# SDC_1.net
KiCad netlist of a schematic drawn in Altium Designer
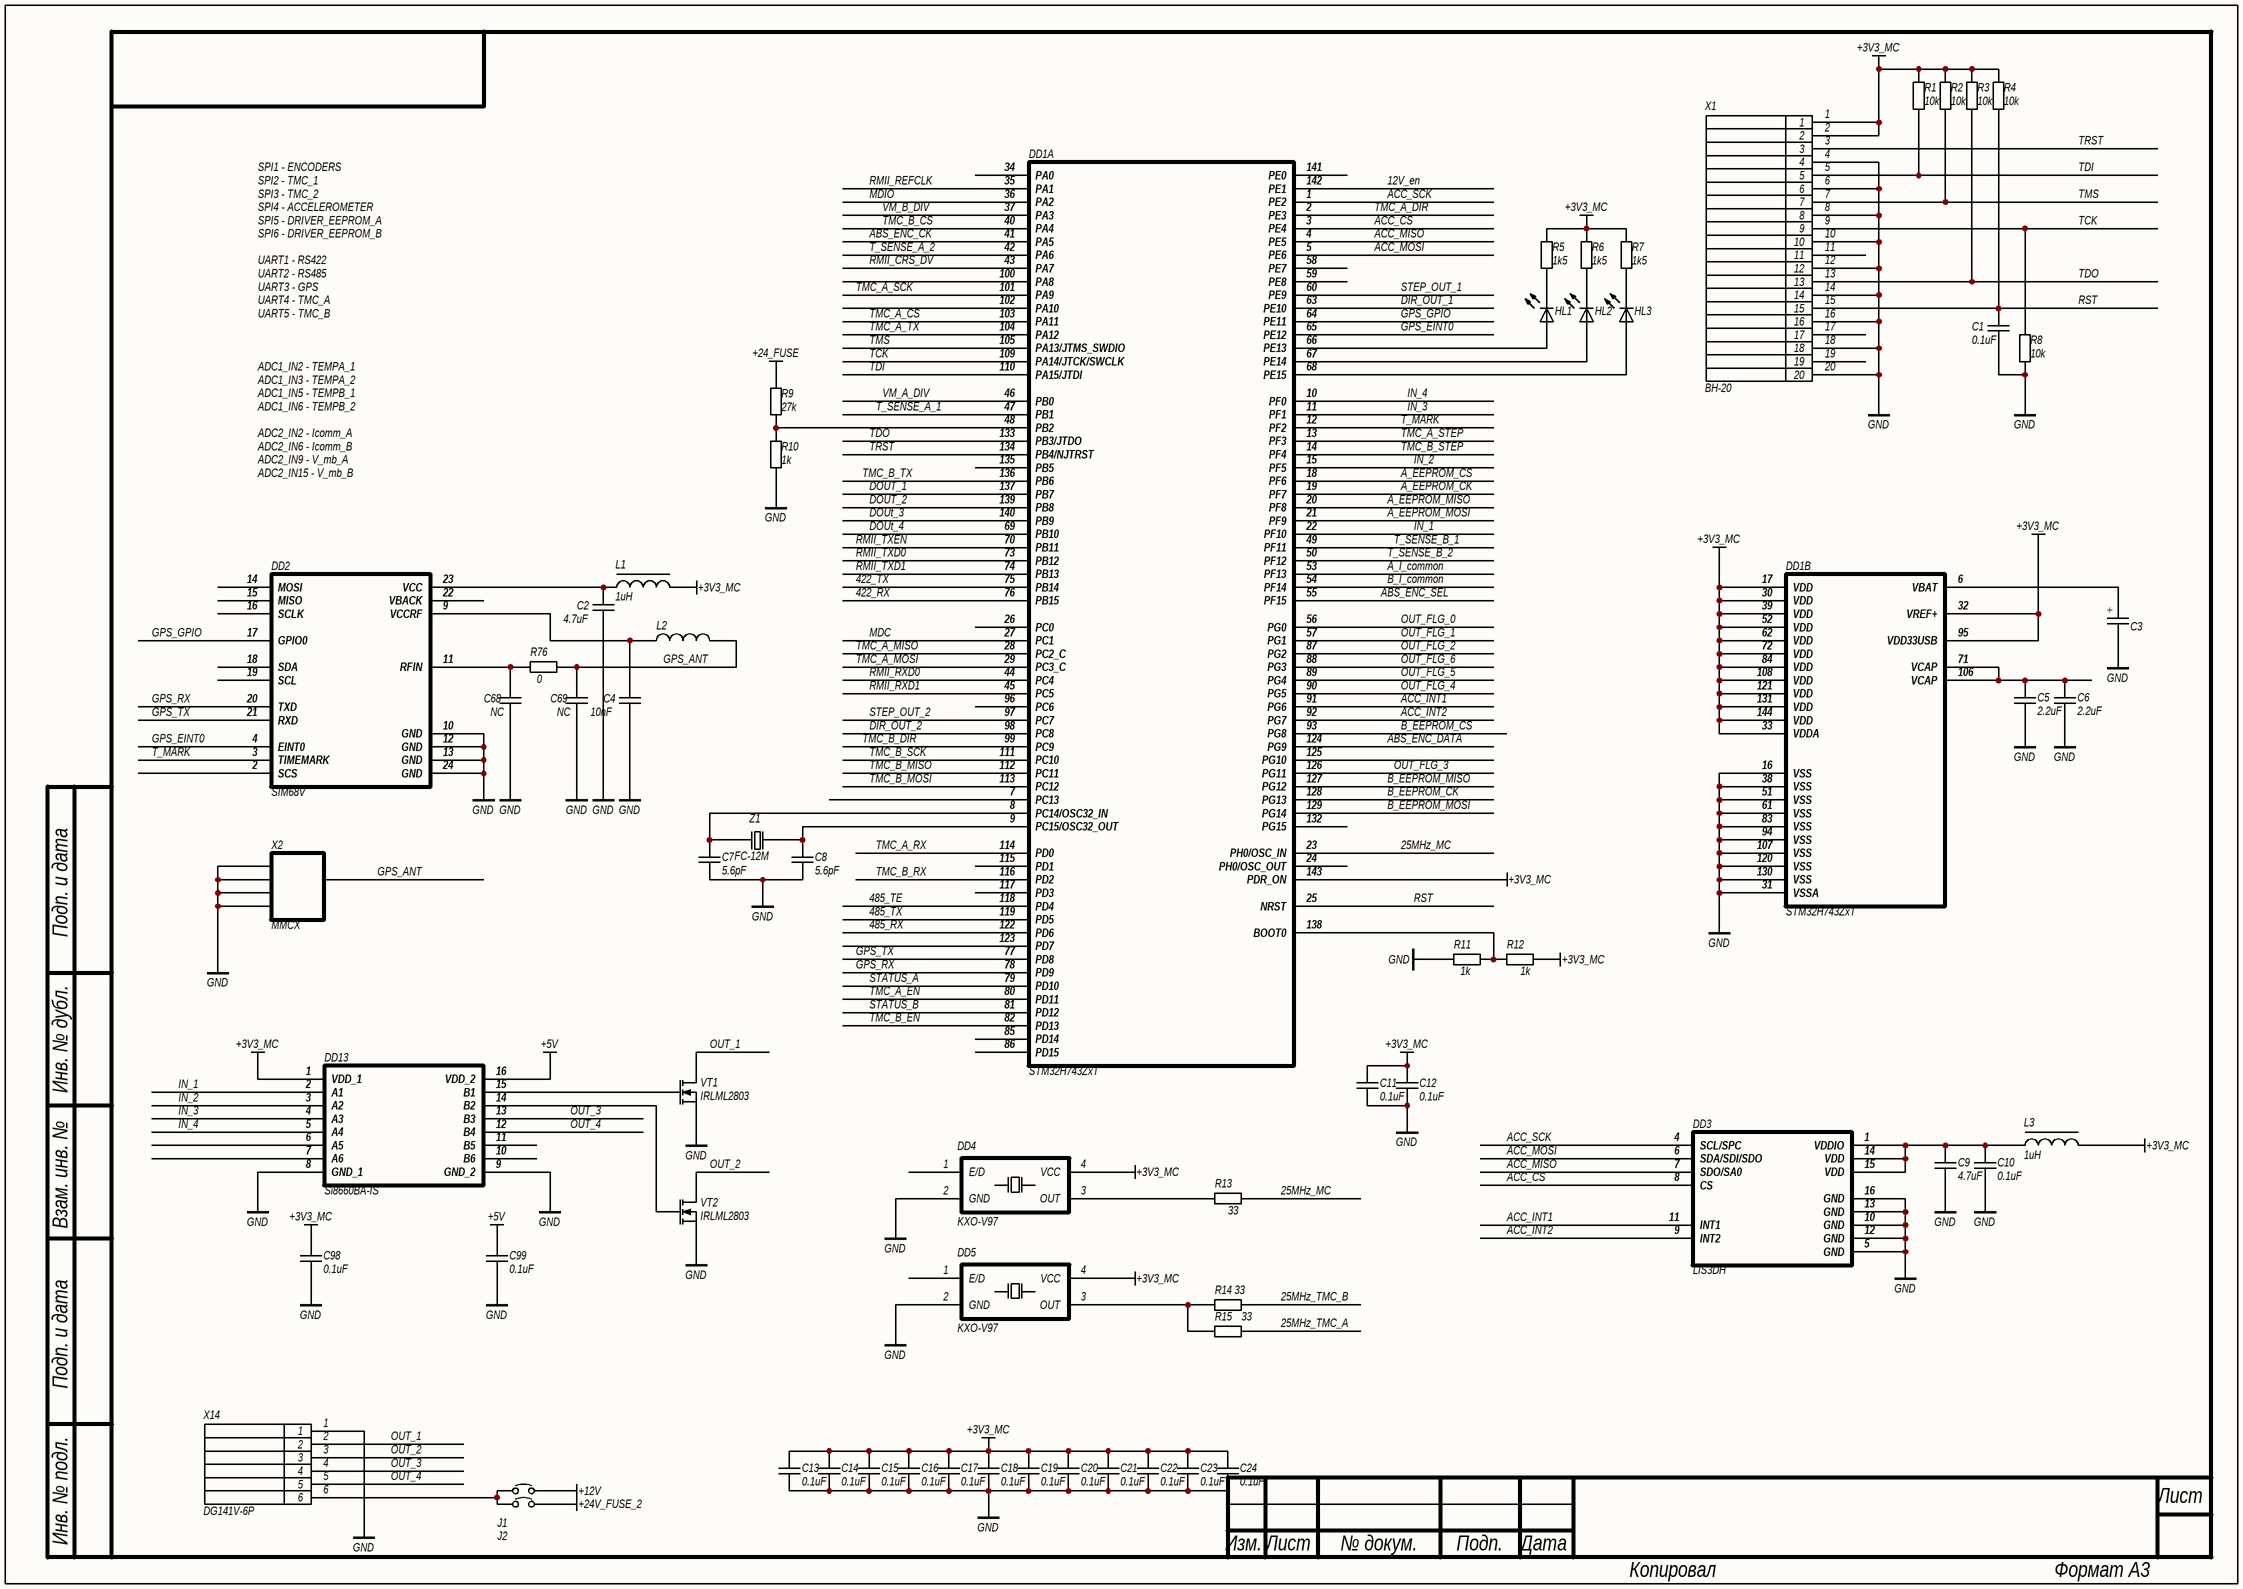
[diagram p0: SDC_1.SchDoc]

(export (version "E")
  (design (tool "Eeschema 10.0.6"))
  (components
    (comp (ref "C1")
      (value "0.1uF")
      (footprint "C0603")
      (description "SMD Capacitor")
      (fields (field (name "MANUFACTURER") "Murata") (field (name "TOLERANCE") "10%"))
      (libsource (lib "VKA") (part "CAP"))
    )
    (comp (ref "C2")
      (value "4.7uF")
      (footprint "C0603")
      (description "SMD Capacitor")
      (fields (field (name "MANUFACTURER") "Murata") (field (name "TOLERANCE") "10%"))
      (libsource (lib "VKA") (part "CAP"))
    )
    (comp (ref "C3")
      (value "KR-5R5H155-R")
      (footprint "KR-5R5H155-R")
      (description "Ionistor")
      (fields (field (name "MANUFACTURER") "Murata") (field (name "VOLTAGE") "5V"))
      (libsource (lib "VKA") (part "KR-5R5H155-R"))
    )
    (comp (ref "C4")
      (value "10nF")
      (footprint "C0603")
      (description "SMD Capacitor")
      (fields (field (name "MANUFACTURER") "Murata") (field (name "TOLERANCE") "10%"))
      (libsource (lib "VKA") (part "CAP"))
    )
    (comp (ref "C5")
      (value "2.2uF")
      (footprint "C0603")
      (description "SMD Capacitor")
      (fields (field (name "MANUFACTURER") "Murata") (field (name "TOLERANCE") "10%"))
      (libsource (lib "VKA") (part "CAP"))
    )
    (comp (ref "C6")
      (value "2.2uF")
      (footprint "C0603")
      (description "SMD Capacitor")
      (fields (field (name "MANUFACTURER") "Murata") (field (name "TOLERANCE") "10%"))
      (libsource (lib "VKA") (part "CAP"))
    )
    (comp (ref "C7")
      (value "5.6pF")
      (footprint "C0603")
      (description "SMD Capacitor")
      (fields (field (name "MANUFACTURER") "Murata") (field (name "TOLERANCE") "10%"))
      (libsource (lib "VKA") (part "CAP"))
    )
    (comp (ref "C8")
      (value "5.6pF")
      (footprint "C0603")
      (description "SMD Capacitor")
      (fields (field (name "MANUFACTURER") "Murata") (field (name "TOLERANCE") "10%"))
      (libsource (lib "VKA") (part "CAP"))
    )
    (comp (ref "C9")
      (value "4.7uF")
      (footprint "C0603")
      (description "SMD Capacitor")
      (fields (field (name "MANUFACTURER") "Murata") (field (name "TOLERANCE") "10%"))
      (libsource (lib "VKA") (part "CAP"))
    )
    (comp (ref "C10")
      (value "0.1uF")
      (footprint "C0603")
      (description "SMD Capacitor")
      (fields (field (name "MANUFACTURER") "Murata") (field (name "TOLERANCE") "10%"))
      (libsource (lib "VKA") (part "CAP"))
    )
    (comp (ref "C11")
      (value "0.1uF")
      (footprint "C0603")
      (description "SMD Capacitor")
      (fields (field (name "MANUFACTURER") "Murata") (field (name "TOLERANCE") "10%"))
      (libsource (lib "VKA") (part "CAP"))
    )
    (comp (ref "C12")
      (value "0.1uF")
      (footprint "C0603")
      (description "SMD Capacitor")
      (fields (field (name "MANUFACTURER") "Murata") (field (name "TOLERANCE") "10%"))
      (libsource (lib "VKA") (part "CAP"))
    )
    (comp (ref "C13")
      (value "0.1uF")
      (footprint "C0603")
      (description "SMD Capacitor")
      (fields (field (name "MANUFACTURER") "Murata") (field (name "TOLERANCE") "10%"))
      (libsource (lib "VKA") (part "CAP"))
    )
    (comp (ref "C14")
      (value "0.1uF")
      (footprint "C0603")
      (description "SMD Capacitor")
      (fields (field (name "MANUFACTURER") "Murata") (field (name "TOLERANCE") "10%"))
      (libsource (lib "VKA") (part "CAP"))
    )
    (comp (ref "C15")
      (value "0.1uF")
      (footprint "C0603")
      (description "SMD Capacitor")
      (fields (field (name "MANUFACTURER") "Murata") (field (name "TOLERANCE") "10%"))
      (libsource (lib "VKA") (part "CAP"))
    )
    (comp (ref "C16")
      (value "0.1uF")
      (footprint "C0603")
      (description "SMD Capacitor")
      (fields (field (name "MANUFACTURER") "Murata") (field (name "TOLERANCE") "10%"))
      (libsource (lib "VKA") (part "CAP"))
    )
    (comp (ref "C17")
      (value "0.1uF")
      (footprint "C0603")
      (description "SMD Capacitor")
      (fields (field (name "MANUFACTURER") "Murata") (field (name "TOLERANCE") "10%"))
      (libsource (lib "VKA") (part "CAP"))
    )
    (comp (ref "C18")
      (value "0.1uF")
      (footprint "C0603")
      (description "SMD Capacitor")
      (fields (field (name "MANUFACTURER") "Murata") (field (name "TOLERANCE") "10%"))
      (libsource (lib "VKA") (part "CAP"))
    )
    (comp (ref "C19")
      (value "0.1uF")
      (footprint "C0603")
      (description "SMD Capacitor")
      (fields (field (name "MANUFACTURER") "Murata") (field (name "TOLERANCE") "10%"))
      (libsource (lib "VKA") (part "CAP"))
    )
    (comp (ref "C20")
      (value "0.1uF")
      (footprint "C0603")
      (description "SMD Capacitor")
      (fields (field (name "MANUFACTURER") "Murata") (field (name "TOLERANCE") "10%"))
      (libsource (lib "VKA") (part "CAP"))
    )
    (comp (ref "C21")
      (value "0.1uF")
      (footprint "C0603")
      (description "SMD Capacitor")
      (fields (field (name "MANUFACTURER") "Murata") (field (name "TOLERANCE") "10%"))
      (libsource (lib "VKA") (part "CAP"))
    )
    (comp (ref "C22")
      (value "0.1uF")
      (footprint "C0603")
      (description "SMD Capacitor")
      (fields (field (name "MANUFACTURER") "Murata") (field (name "TOLERANCE") "10%"))
      (libsource (lib "VKA") (part "CAP"))
    )
    (comp (ref "C23")
      (value "0.1uF")
      (footprint "C0603")
      (description "SMD Capacitor")
      (fields (field (name "MANUFACTURER") "Murata") (field (name "TOLERANCE") "10%"))
      (libsource (lib "VKA") (part "CAP"))
    )
    (comp (ref "C24")
      (value "0.1uF")
      (footprint "C0603")
      (description "SMD Capacitor")
      (fields (field (name "MANUFACTURER") "Murata") (field (name "TOLERANCE") "10%"))
      (libsource (lib "VKA") (part "CAP"))
    )
    (comp (ref "C68")
      (value "NC")
      (footprint "C0603")
      (description "SMD Capacitor")
      (fields (field (name "MANUFACTURER") "Murata") (field (name "TOLERANCE") "10%"))
      (libsource (lib "VKA") (part "CAP"))
    )
    (comp (ref "C69")
      (value "NC")
      (footprint "C0603")
      (description "SMD Capacitor")
      (fields (field (name "MANUFACTURER") "Murata") (field (name "TOLERANCE") "10%"))
      (libsource (lib "VKA") (part "CAP"))
    )
    (comp (ref "C98")
      (value "0.1uF")
      (footprint "C0603")
      (description "SMD Capacitor")
      (fields (field (name "MANUFACTURER") "Murata") (field (name "TOLERANCE") "10%"))
      (libsource (lib "VKA") (part "CAP"))
    )
    (comp (ref "C99")
      (value "0.1uF")
      (footprint "C0603")
      (description "SMD Capacitor")
      (fields (field (name "MANUFACTURER") "Murata") (field (name "TOLERANCE") "10%"))
      (libsource (lib "VKA") (part "CAP"))
    )
    (comp (ref "DD1")
      (value "STM32H743ZxT")
      (footprint "STM-LQFP144_L")
      (description "ARM Cortex-M7, 480MHz, 32-bit MCU+FPU, 144-pin LQFP")
      (libsource (lib "VKA") (part "STM32H743ZxT"))
    )
    (comp (ref "DD2")
      (value "SIM68V")
      (footprint "SIM68M")
      (description "GPS module")
      (libsource (lib "VKA") (part "SIM68V"))
    )
    (comp (ref "DD3")
      (value "LIS3DH")
      (footprint "LGA-16")
      (description "Accelerometer")
      (libsource (lib "VKA") (part "LIS3DH"))
    )
    (comp (ref "DD4")
      (value "KXO-V97")
      (footprint "SO4-GEN")
      (description "KXO generator")
      (libsource (lib "VKA") (part "KXO-V97"))
    )
    (comp (ref "DD5")
      (value "KXO-V97")
      (footprint "SO4-GEN")
      (description "KXO generator")
      (libsource (lib "VKA") (part "KXO-V97"))
    )
    (comp (ref "DD13")
      (value "Si8660BA-IS")
      (footprint "SO-16_N")
      (description "digital isolator")
      (libsource (lib "VKA") (part "Si8660BA-IS"))
    )
    (comp (ref "HL1") (value "LED0603") (footprint "LED0603") (libsource (lib "VKA") (part "LED0603")))
    (comp (ref "HL2") (value "LED0603") (footprint "LED0603") (libsource (lib "VKA") (part "LED0603")))
    (comp (ref "HL3") (value "LED0603") (footprint "LED0603") (libsource (lib "VKA") (part "LED0603")))
    (comp (ref "J1") (value "JUMP") (footprint "JUMP") (libsource (lib "VKA") (part "JUMP")))
    (comp (ref "J2") (value "JUMP") (footprint "JUMP") (libsource (lib "VKA") (part "JUMP")))
    (comp (ref "L1")
      (value "1uH")
      (footprint "LQH32CN")
      (description "chip inductor")
      (fields (field (name "Comment") "LQH32CN"))
      (libsource (lib "VKA") (part "LQH32CN"))
    )
    (comp (ref "L2")
      (value "FerriteBead")
      (footprint "L0603")
      (description "SMD Chip ferrite bead 0603")
      (libsource (lib "VKA") (part "FerriteBead"))
    )
    (comp (ref "L3")
      (value "1uH")
      (footprint "LQH32CN")
      (description "chip inductor")
      (fields (field (name "Comment") "LQH32CN"))
      (libsource (lib "VKA") (part "LQH32CN"))
    )
    (comp (ref "R1")
      (value "10k")
      (footprint "R0603")
      (description "SMD Resistor")
      (fields (field (name "POWER") "0.062 Wt") (field (name "TOLERANCE") "5%"))
      (libsource (lib "VKA") (part "RES"))
    )
    (comp (ref "R2")
      (value "10k")
      (footprint "R0603")
      (description "SMD Resistor")
      (fields (field (name "POWER") "0.062 Wt") (field (name "TOLERANCE") "5%"))
      (libsource (lib "VKA") (part "RES"))
    )
    (comp (ref "R3")
      (value "10k")
      (footprint "R0603")
      (description "SMD Resistor")
      (fields (field (name "POWER") "0.062 Wt") (field (name "TOLERANCE") "5%"))
      (libsource (lib "VKA") (part "RES"))
    )
    (comp (ref "R4")
      (value "10k")
      (footprint "R0603")
      (description "SMD Resistor")
      (fields (field (name "POWER") "0.062 Wt") (field (name "TOLERANCE") "5%"))
      (libsource (lib "VKA") (part "RES"))
    )
    (comp (ref "R5")
      (value "1k5")
      (footprint "R0603")
      (description "SMD Resistor")
      (fields (field (name "POWER") "0.062 Wt") (field (name "TOLERANCE") "5%"))
      (libsource (lib "VKA") (part "RES"))
    )
    (comp (ref "R6")
      (value "1k5")
      (footprint "R0603")
      (description "SMD Resistor")
      (fields (field (name "POWER") "0.062 Wt") (field (name "TOLERANCE") "5%"))
      (libsource (lib "VKA") (part "RES"))
    )
    (comp (ref "R7")
      (value "1k5")
      (footprint "R0603")
      (description "SMD Resistor")
      (fields (field (name "POWER") "0.062 Wt") (field (name "TOLERANCE") "5%"))
      (libsource (lib "VKA") (part "RES"))
    )
    (comp (ref "R8")
      (value "10k")
      (footprint "R0603")
      (description "SMD Resistor")
      (fields (field (name "POWER") "0.062 Wt") (field (name "TOLERANCE") "5%"))
      (libsource (lib "VKA") (part "RES"))
    )
    (comp (ref "R9")
      (value "27k")
      (footprint "R0603")
      (description "SMD Resistor")
      (fields (field (name "POWER") "0.062 Wt") (field (name "TOLERANCE") "5%"))
      (libsource (lib "") (part "RES_2"))
    )
    (comp (ref "R10")
      (value "1k")
      (footprint "R0603")
      (description "SMD Resistor")
      (fields (field (name "POWER") "0.062 Wt") (field (name "TOLERANCE") "5%"))
      (libsource (lib "") (part "RES_2"))
    )
    (comp (ref "R11")
      (value "1k")
      (footprint "R0603")
      (description "SMD Resistor")
      (fields (field (name "POWER") "0.062 Wt") (field (name "TOLERANCE") "5%"))
      (libsource (lib "") (part "RES_1"))
    )
    (comp (ref "R12")
      (value "1k")
      (footprint "R0603")
      (description "SMD Resistor")
      (fields (field (name "POWER") "0.062 Wt") (field (name "TOLERANCE") "5%"))
      (libsource (lib "") (part "RES_1"))
    )
    (comp (ref "R13")
      (value "33")
      (footprint "R0603")
      (description "SMD Resistor")
      (fields (field (name "POWER") "0.062 Wt") (field (name "TOLERANCE") "5%"))
      (libsource (lib "") (part "RES_1"))
    )
    (comp (ref "R14")
      (value "33")
      (footprint "R0603")
      (description "SMD Resistor")
      (fields (field (name "POWER") "0.062 Wt") (field (name "TOLERANCE") "5%"))
      (libsource (lib "") (part "RES_1"))
    )
    (comp (ref "R15")
      (value "33")
      (footprint "R0603")
      (description "SMD Resistor")
      (fields (field (name "POWER") "0.062 Wt") (field (name "TOLERANCE") "5%"))
      (libsource (lib "") (part "RES_1"))
    )
    (comp (ref "R76")
      (value "0")
      (footprint "R0603")
      (description "SMD Resistor")
      (fields (field (name "POWER") "0.062 Wt") (field (name "TOLERANCE") "5%"))
      (libsource (lib "") (part "RES_1"))
    )
    (comp (ref "VT1")
      (value "IRLML2803")
      (footprint "SOT23")
      (description "n-channel fet")
      (libsource (lib "VKA") (part "IRLML2803"))
    )
    (comp (ref "VT2")
      (value "IRLML2803")
      (footprint "SOT23")
      (description "n-channel fet")
      (libsource (lib "VKA") (part "IRLML2803"))
    )
    (comp (ref "X1")
      (value "BH-20")
      (footprint "IDC-20(BH-20)")
      (libsource (lib "VKA") (part "IDC10x2_GOST"))
    )
    (comp (ref "X2")
      (value "MMCX")
      (footprint "MMCX")
      (description "Coaxial")
      (libsource (lib "VKA") (part "MMCX"))
    )
    (comp (ref "X14")
      (value "DG141V-6P")
      (footprint "DG141V-06P")
      (description "wire connector")
      (libsource (lib "VKA") (part "DG141V-6P"))
    )
    (comp (ref "Z1")
      (value "FC-12M")
      (footprint "FC-12M")
      (description "Crystal_32_768")
      (libsource (lib "VKA") (part "FC-12M"))
    )
  )
  (nets
    (net (code "1") (name "+3V3_MC") (class "Default")
      (node (ref "C11") (pin "2") (pinfunction "2_2") (pintype "passive"))
      (node (ref "C12") (pin "2") (pinfunction "2_2") (pintype "passive"))
      (node (ref "C13") (pin "2") (pinfunction "2_2") (pintype "passive"))
      (node (ref "C14") (pin "2") (pinfunction "2_2") (pintype "passive"))
      (node (ref "C15") (pin "2") (pinfunction "2_2") (pintype "passive"))
      (node (ref "C16") (pin "2") (pinfunction "2_2") (pintype "passive"))
      (node (ref "C17") (pin "2") (pinfunction "2_2") (pintype "passive"))
      (node (ref "C18") (pin "2") (pinfunction "2_2") (pintype "passive"))
      (node (ref "C19") (pin "2") (pinfunction "2_2") (pintype "passive"))
      (node (ref "C20") (pin "2") (pinfunction "2_2") (pintype "passive"))
      (node (ref "C21") (pin "2") (pinfunction "2_2") (pintype "passive"))
      (node (ref "C22") (pin "2") (pinfunction "2_2") (pintype "passive"))
      (node (ref "C23") (pin "2") (pinfunction "2_2") (pintype "passive"))
      (node (ref "C24") (pin "2") (pinfunction "2_2") (pintype "passive"))
      (node (ref "C98") (pin "2") (pinfunction "2_2") (pintype "passive"))
      (node (ref "DD1") (pin "108") (pinfunction "VDD_108") (pintype "passive"))
      (node (ref "DD1") (pin "121") (pinfunction "VDD_121") (pintype "passive"))
      (node (ref "DD1") (pin "131") (pinfunction "VDD_131") (pintype "passive"))
      (node (ref "DD1") (pin "143") (pinfunction "PDR_ON_143") (pintype "passive"))
      (node (ref "DD1") (pin "144") (pinfunction "VDD_144") (pintype "passive"))
      (node (ref "DD1") (pin "17") (pinfunction "VDD_17") (pintype "passive"))
      (node (ref "DD1") (pin "30") (pinfunction "VDD_30") (pintype "passive"))
      (node (ref "DD1") (pin "32") (pinfunction "VREF+_32") (pintype "passive"))
      (node (ref "DD1") (pin "33") (pinfunction "VDDA_33") (pintype "passive"))
      (node (ref "DD1") (pin "39") (pinfunction "VDD_39") (pintype "passive"))
      (node (ref "DD1") (pin "52") (pinfunction "VDD_52") (pintype "passive"))
      (node (ref "DD1") (pin "62") (pinfunction "VDD_62") (pintype "passive"))
      (node (ref "DD1") (pin "72") (pinfunction "VDD_72") (pintype "passive"))
      (node (ref "DD1") (pin "84") (pinfunction "VDD_84") (pintype "passive"))
      (node (ref "DD1") (pin "95") (pinfunction "VDD33USB_95") (pintype "passive"))
      (node (ref "DD13") (pin "1") (pinfunction "VDD_1_1") (pintype "passive"))
      (node (ref "DD4") (pin "4") (pinfunction "VCC_4") (pintype "passive"))
      (node (ref "DD5") (pin "4") (pinfunction "VCC_4") (pintype "passive"))
      (node (ref "L1") (pin "2") (pinfunction "2_2") (pintype "passive"))
      (node (ref "L3") (pin "2") (pinfunction "2_2") (pintype "passive"))
      (node (ref "R1") (pin "1") (pinfunction "1_1") (pintype "passive"))
      (node (ref "R12") (pin "1") (pinfunction "1_1") (pintype "passive"))
      (node (ref "R2") (pin "1") (pinfunction "1_1") (pintype "passive"))
      (node (ref "R3") (pin "1") (pinfunction "1_1") (pintype "passive"))
      (node (ref "R4") (pin "1") (pinfunction "1_1") (pintype "passive"))
      (node (ref "R5") (pin "1") (pinfunction "1_1") (pintype "passive"))
      (node (ref "R6") (pin "1") (pinfunction "1_1") (pintype "passive"))
      (node (ref "R7") (pin "1") (pinfunction "1_1") (pintype "passive"))
      (node (ref "X1") (pin "1") (pinfunction "1_1") (pintype "passive"))
      (node (ref "X1") (pin "2") (pinfunction "2_2") (pintype "passive"))
    )
    (net (code "2") (name "+5V") (class "Default")
      (node (ref "C99") (pin "2") (pinfunction "2_2") (pintype "passive"))
      (node (ref "DD13") (pin "16") (pinfunction "VDD_2_16") (pintype "passive"))
    )
    (net (code "3") (name "+12V") (class "Default")
      (node (ref "J1") (pin "2") (pinfunction "2_2") (pintype "passive"))
    )
    (net (code "4") (name "+24V_FUSE_2") (class "Default")
      (node (ref "J2") (pin "2") (pinfunction "2_2") (pintype "passive"))
    )
    (net (code "5") (name "+24_FUSE") (class "Default")
      (node (ref "R9") (pin "2") (pinfunction "2_2") (pintype "passive"))
    )
    (net (code "6") (name "/12V_en") (class "Default")
      (node (ref "DD1") (pin "142") (pinfunction "PE1_142") (pintype "passive"))
    )
    (net (code "7") (name "/25MHz_MC") (class "Default")
      (node (ref "DD1") (pin "23") (pinfunction "PH0/OSC_IN_23") (pintype "passive"))
      (node (ref "R13") (pin "1") (pinfunction "1_1") (pintype "passive"))
    )
    (net (code "8") (name "/25MHz_TMC_A") (class "Default")
      (node (ref "R15") (pin "1") (pinfunction "1_1") (pintype "passive"))
    )
    (net (code "9") (name "/25MHz_TMC_B") (class "Default")
      (node (ref "R14") (pin "1") (pinfunction "1_1") (pintype "passive"))
    )
    (net (code "10") (name "/422_RX") (class "Default")
      (node (ref "DD1") (pin "76") (pinfunction "PB15_76") (pintype "passive"))
    )
    (net (code "11") (name "/422_TX") (class "Default")
      (node (ref "DD1") (pin "75") (pinfunction "PB14_75") (pintype "passive"))
    )
    (net (code "12") (name "/485_RX") (class "Default")
      (node (ref "DD1") (pin "122") (pinfunction "PD6_122") (pintype "passive"))
    )
    (net (code "13") (name "/485_TE") (class "Default")
      (node (ref "DD1") (pin "118") (pinfunction "PD4_118") (pintype "passive"))
    )
    (net (code "14") (name "/485_TX") (class "Default")
      (node (ref "DD1") (pin "119") (pinfunction "PD5_119") (pintype "passive"))
    )
    (net (code "15") (name "/ABS_ENC_CK") (class "Default")
      (node (ref "DD1") (pin "41") (pinfunction "PA5_41") (pintype "passive"))
    )
    (net (code "16") (name "/ABS_ENC_DATA") (class "Default")
      (node (ref "DD1") (pin "124") (pinfunction "PG9_124") (pintype "passive"))
    )
    (net (code "17") (name "/ABS_ENC_SEL") (class "Default")
      (node (ref "DD1") (pin "55") (pinfunction "PF15_55") (pintype "passive"))
    )
    (net (code "18") (name "/ACC_CS") (class "Default")
      (node (ref "DD1") (pin "3") (pinfunction "PE4_3") (pintype "passive"))
      (node (ref "DD3") (pin "8") (pinfunction "CS_8") (pintype "passive"))
    )
    (net (code "19") (name "/ACC_INT1") (class "Default")
      (node (ref "DD1") (pin "91") (pinfunction "PG6_91") (pintype "passive"))
      (node (ref "DD3") (pin "11") (pinfunction "INT1_11") (pintype "passive"))
    )
    (net (code "20") (name "/ACC_INT2") (class "Default")
      (node (ref "DD1") (pin "92") (pinfunction "PG7_92") (pintype "passive"))
      (node (ref "DD3") (pin "9") (pinfunction "INT2_9") (pintype "passive"))
    )
    (net (code "21") (name "/ACC_MISO") (class "Default")
      (node (ref "DD1") (pin "4") (pinfunction "PE5_4") (pintype "passive"))
      (node (ref "DD3") (pin "7") (pinfunction "SDO/SA0_7") (pintype "passive"))
    )
    (net (code "22") (name "/ACC_MOSI") (class "Default")
      (node (ref "DD1") (pin "5") (pinfunction "PE6_5") (pintype "passive"))
      (node (ref "DD3") (pin "6") (pinfunction "SDA/SDI/SDO_6") (pintype "passive"))
    )
    (net (code "23") (name "/ACC_SCK") (class "Default")
      (node (ref "DD1") (pin "1") (pinfunction "PE2_1") (pintype "passive"))
      (node (ref "DD3") (pin "4") (pinfunction "SCL/SPC_4") (pintype "passive"))
    )
    (net (code "24") (name "/A_EEPROM_CK") (class "Default")
      (node (ref "DD1") (pin "19") (pinfunction "PF7_19") (pintype "passive"))
    )
    (net (code "25") (name "/A_EEPROM_CS") (class "Default")
      (node (ref "DD1") (pin "18") (pinfunction "PF6_18") (pintype "passive"))
    )
    (net (code "26") (name "/A_EEPROM_MISO") (class "Default")
      (node (ref "DD1") (pin "20") (pinfunction "PF8_20") (pintype "passive"))
    )
    (net (code "27") (name "/A_EEPROM_MOSI") (class "Default")
      (node (ref "DD1") (pin "21") (pinfunction "PF9_21") (pintype "passive"))
    )
    (net (code "28") (name "/A_I_common") (class "Default")
      (node (ref "DD1") (pin "53") (pinfunction "PF13_53") (pintype "passive"))
    )
    (net (code "29") (name "/B_EEPROM_CK") (class "Default")
      (node (ref "DD1") (pin "128") (pinfunction "PG13_128") (pintype "passive"))
    )
    (net (code "30") (name "/B_EEPROM_CS") (class "Default")
      (node (ref "DD1") (pin "93") (pinfunction "PG8_93") (pintype "passive"))
    )
    (net (code "31") (name "/B_EEPROM_MISO") (class "Default")
      (node (ref "DD1") (pin "127") (pinfunction "PG12_127") (pintype "passive"))
    )
    (net (code "32") (name "/B_EEPROM_MOSI") (class "Default")
      (node (ref "DD1") (pin "129") (pinfunction "PG14_129") (pintype "passive"))
    )
    (net (code "33") (name "/B_I_common") (class "Default")
      (node (ref "DD1") (pin "54") (pinfunction "PF14_54") (pintype "passive"))
    )
    (net (code "34") (name "/DIR_OUT_1") (class "Default")
      (node (ref "DD1") (pin "63") (pinfunction "PE10_63") (pintype "passive"))
    )
    (net (code "35") (name "/DIR_OUT_2") (class "Default")
      (node (ref "DD1") (pin "98") (pinfunction "PC8_98") (pintype "passive"))
    )
    (net (code "36") (name "/DOUT_1") (class "Default")
      (node (ref "DD1") (pin "137") (pinfunction "PB7_137") (pintype "passive"))
    )
    (net (code "37") (name "/DOUT_2") (class "Default")
      (node (ref "DD1") (pin "139") (pinfunction "PB8_139") (pintype "passive"))
    )
    (net (code "38") (name "/DOUt_3") (class "Default")
      (node (ref "DD1") (pin "140") (pinfunction "PB9_140") (pintype "passive"))
    )
    (net (code "39") (name "/DOUt_4") (class "Default")
      (node (ref "DD1") (pin "69") (pinfunction "PB10_69") (pintype "passive"))
    )
    (net (code "40") (name "/GPS_ANT") (class "Default")
      (node (ref "C69") (pin "2") (pinfunction "2_2") (pintype "passive"))
      (node (ref "L2") (pin "2") (pinfunction "2_2") (pintype "passive"))
      (node (ref "R76") (pin "1") (pinfunction "1_1") (pintype "passive"))
      (node (ref "X2") (pin "5") (pinfunction "SYG_5") (pintype "passive"))
    )
    (net (code "41") (name "/GPS_EINT0") (class "Default")
      (node (ref "DD1") (pin "65") (pinfunction "PE12_65") (pintype "passive"))
      (node (ref "DD2") (pin "4") (pinfunction "EINT0_4") (pintype "passive"))
    )
    (net (code "42") (name "/GPS_GPIO") (class "Default")
      (node (ref "DD1") (pin "64") (pinfunction "PE11_64") (pintype "passive"))
      (node (ref "DD2") (pin "17") (pinfunction "GPIO0_17") (pintype "passive"))
    )
    (net (code "43") (name "/GPS_RX") (class "Default")
      (node (ref "DD1") (pin "78") (pinfunction "PD9_78") (pintype "passive"))
      (node (ref "DD2") (pin "20") (pinfunction "TXD_20") (pintype "passive"))
    )
    (net (code "44") (name "/GPS_TX") (class "Default")
      (node (ref "DD1") (pin "77") (pinfunction "PD8_77") (pintype "passive"))
      (node (ref "DD2") (pin "21") (pinfunction "RXD_21") (pintype "passive"))
    )
    (net (code "45") (name "/IN_1") (class "Default")
      (node (ref "DD1") (pin "22") (pinfunction "PF10_22") (pintype "passive"))
      (node (ref "DD13") (pin "2") (pinfunction "A1_2") (pintype "passive"))
    )
    (net (code "46") (name "/IN_2") (class "Default")
      (node (ref "DD1") (pin "15") (pinfunction "PF5_15") (pintype "passive"))
      (node (ref "DD13") (pin "3") (pinfunction "A2_3") (pintype "passive"))
    )
    (net (code "47") (name "/IN_3") (class "Default")
      (node (ref "DD1") (pin "11") (pinfunction "PF1_11") (pintype "passive"))
      (node (ref "DD13") (pin "4") (pinfunction "A3_4") (pintype "passive"))
    )
    (net (code "48") (name "/IN_4") (class "Default")
      (node (ref "DD1") (pin "10") (pinfunction "PF0_10") (pintype "passive"))
      (node (ref "DD13") (pin "5") (pinfunction "A4_5") (pintype "passive"))
    )
    (net (code "49") (name "/MDC") (class "Default")
      (node (ref "DD1") (pin "27") (pinfunction "PC1_27") (pintype "passive"))
    )
    (net (code "50") (name "/MDIO") (class "Default")
      (node (ref "DD1") (pin "36") (pinfunction "PA2_36") (pintype "passive"))
    )
    (net (code "51") (name "/OUT_1") (class "Default")
      (node (ref "VT1") (pin "3") (pinfunction "D_3") (pintype "passive"))
      (node (ref "X14") (pin "2") (pinfunction "2_2") (pintype "passive"))
    )
    (net (code "52") (name "/OUT_2") (class "Default")
      (node (ref "VT2") (pin "3") (pinfunction "D_3") (pintype "passive"))
      (node (ref "X14") (pin "3") (pinfunction "3_3") (pintype "passive"))
    )
    (net (code "53") (name "/OUT_3") (class "Default")
      (node (ref "DD13") (pin "13") (pinfunction "B3_13") (pintype "passive"))
      (node (ref "X14") (pin "4") (pinfunction "4_4") (pintype "passive"))
    )
    (net (code "54") (name "/OUT_4") (class "Default")
      (node (ref "DD13") (pin "12") (pinfunction "B4_12") (pintype "passive"))
      (node (ref "X14") (pin "5") (pinfunction "5_5") (pintype "passive"))
    )
    (net (code "55") (name "/OUT_FLG_0") (class "Default")
      (node (ref "DD1") (pin "56") (pinfunction "PG0_56") (pintype "passive"))
    )
    (net (code "56") (name "/OUT_FLG_1") (class "Default")
      (node (ref "DD1") (pin "57") (pinfunction "PG1_57") (pintype "passive"))
    )
    (net (code "57") (name "/OUT_FLG_2") (class "Default")
      (node (ref "DD1") (pin "87") (pinfunction "PG2_87") (pintype "passive"))
    )
    (net (code "58") (name "/OUT_FLG_3") (class "Default")
      (node (ref "DD1") (pin "126") (pinfunction "PG11_126") (pintype "passive"))
    )
    (net (code "59") (name "/OUT_FLG_4") (class "Default")
      (node (ref "DD1") (pin "90") (pinfunction "PG5_90") (pintype "passive"))
    )
    (net (code "60") (name "/OUT_FLG_5") (class "Default")
      (node (ref "DD1") (pin "89") (pinfunction "PG4_89") (pintype "passive"))
    )
    (net (code "61") (name "/OUT_FLG_6") (class "Default")
      (node (ref "DD1") (pin "88") (pinfunction "PG3_88") (pintype "passive"))
    )
    (net (code "62") (name "/RMII_CRS_DV") (class "Default")
      (node (ref "DD1") (pin "43") (pinfunction "PA7_43") (pintype "passive"))
    )
    (net (code "63") (name "/RMII_REFCLK") (class "Default")
      (node (ref "DD1") (pin "35") (pinfunction "PA1_35") (pintype "passive"))
    )
    (net (code "64") (name "/RMII_RXD0") (class "Default")
      (node (ref "DD1") (pin "44") (pinfunction "PC4_44") (pintype "passive"))
    )
    (net (code "65") (name "/RMII_RXD1") (class "Default")
      (node (ref "DD1") (pin "45") (pinfunction "PC5_45") (pintype "passive"))
    )
    (net (code "66") (name "/RMII_TXD0") (class "Default")
      (node (ref "DD1") (pin "73") (pinfunction "PB12_73") (pintype "passive"))
    )
    (net (code "67") (name "/RMII_TXD1") (class "Default")
      (node (ref "DD1") (pin "74") (pinfunction "PB13_74") (pintype "passive"))
    )
    (net (code "68") (name "/RMII_TXEN") (class "Default")
      (node (ref "DD1") (pin "70") (pinfunction "PB11_70") (pintype "passive"))
    )
    (net (code "69") (name "/RST") (class "Default")
      (node (ref "C1") (pin "2") (pinfunction "2_2") (pintype "passive"))
      (node (ref "DD1") (pin "25") (pinfunction "NRST_25") (pintype "passive"))
      (node (ref "R4") (pin "2") (pinfunction "2_2") (pintype "passive"))
      (node (ref "X1") (pin "15") (pinfunction "15_15") (pintype "passive"))
    )
    (net (code "70") (name "/STATUS_A") (class "Default")
      (node (ref "DD1") (pin "79") (pinfunction "PD10_79") (pintype "passive"))
    )
    (net (code "71") (name "/STATUS_B") (class "Default")
      (node (ref "DD1") (pin "81") (pinfunction "PD12_81") (pintype "passive"))
    )
    (net (code "72") (name "/STEP_OUT_1") (class "Default")
      (node (ref "DD1") (pin "60") (pinfunction "PE9_60") (pintype "passive"))
    )
    (net (code "73") (name "/STEP_OUT_2") (class "Default")
      (node (ref "DD1") (pin "97") (pinfunction "PC7_97") (pintype "passive"))
    )
    (net (code "74") (name "/TCK") (class "Default")
      (node (ref "DD1") (pin "109") (pinfunction "PA14/JTCK/SWCLK_109") (pintype "passive"))
      (node (ref "R8") (pin "1") (pinfunction "1_1") (pintype "passive"))
      (node (ref "X1") (pin "9") (pinfunction "9_9") (pintype "passive"))
    )
    (net (code "75") (name "/TDI") (class "Default")
      (node (ref "DD1") (pin "110") (pinfunction "PA15/JTDI_110") (pintype "passive"))
      (node (ref "R1") (pin "2") (pinfunction "2_2") (pintype "passive"))
      (node (ref "X1") (pin "5") (pinfunction "5_5") (pintype "passive"))
    )
    (net (code "76") (name "/TDO") (class "Default")
      (node (ref "DD1") (pin "133") (pinfunction "PB3/JTDO_133") (pintype "passive"))
      (node (ref "R3") (pin "2") (pinfunction "2_2") (pintype "passive"))
      (node (ref "X1") (pin "13") (pinfunction "13_13") (pintype "passive"))
    )
    (net (code "77") (name "/TMC_A_CS") (class "Default")
      (node (ref "DD1") (pin "103") (pinfunction "PA11_103") (pintype "passive"))
    )
    (net (code "78") (name "/TMC_A_DIR") (class "Default")
      (node (ref "DD1") (pin "2") (pinfunction "PE3_2") (pintype "passive"))
    )
    (net (code "79") (name "/TMC_A_EN") (class "Default")
      (node (ref "DD1") (pin "80") (pinfunction "PD11_80") (pintype "passive"))
    )
    (net (code "80") (name "/TMC_A_MISO") (class "Default")
      (node (ref "DD1") (pin "28") (pinfunction "PC2_C_28") (pintype "passive"))
    )
    (net (code "81") (name "/TMC_A_MOSI") (class "Default")
      (node (ref "DD1") (pin "29") (pinfunction "PC3_C_29") (pintype "passive"))
    )
    (net (code "82") (name "/TMC_A_RX") (class "Default")
      (node (ref "DD1") (pin "114") (pinfunction "PD0_114") (pintype "passive"))
    )
    (net (code "83") (name "/TMC_A_SCK") (class "Default")
      (node (ref "DD1") (pin "101") (pinfunction "PA9_101") (pintype "passive"))
    )
    (net (code "84") (name "/TMC_A_STEP") (class "Default")
      (node (ref "DD1") (pin "13") (pinfunction "PF3_13") (pintype "passive"))
    )
    (net (code "85") (name "/TMC_A_TX") (class "Default")
      (node (ref "DD1") (pin "104") (pinfunction "PA12_104") (pintype "passive"))
    )
    (net (code "86") (name "/TMC_B_CS") (class "Default")
      (node (ref "DD1") (pin "40") (pinfunction "PA4_40") (pintype "passive"))
    )
    (net (code "87") (name "/TMC_B_DIR") (class "Default")
      (node (ref "DD1") (pin "99") (pinfunction "PC9_99") (pintype "passive"))
    )
    (net (code "88") (name "/TMC_B_EN") (class "Default")
      (node (ref "DD1") (pin "82") (pinfunction "PD13_82") (pintype "passive"))
    )
    (net (code "89") (name "/TMC_B_MISO") (class "Default")
      (node (ref "DD1") (pin "112") (pinfunction "PC11_112") (pintype "passive"))
    )
    (net (code "90") (name "/TMC_B_MOSI") (class "Default")
      (node (ref "DD1") (pin "113") (pinfunction "PC12_113") (pintype "passive"))
    )
    (net (code "91") (name "/TMC_B_RX") (class "Default")
      (node (ref "DD1") (pin "116") (pinfunction "PD2_116") (pintype "passive"))
    )
    (net (code "92") (name "/TMC_B_SCK") (class "Default")
      (node (ref "DD1") (pin "111") (pinfunction "PC10_111") (pintype "passive"))
    )
    (net (code "93") (name "/TMC_B_STEP") (class "Default")
      (node (ref "DD1") (pin "14") (pinfunction "PF4_14") (pintype "passive"))
    )
    (net (code "94") (name "/TMC_B_TX") (class "Default")
      (node (ref "DD1") (pin "136") (pinfunction "PB6_136") (pintype "passive"))
    )
    (net (code "95") (name "/TMS") (class "Default")
      (node (ref "DD1") (pin "105") (pinfunction "PA13/JTMS_SWDIO_105") (pintype "passive"))
      (node (ref "R2") (pin "2") (pinfunction "2_2") (pintype "passive"))
      (node (ref "X1") (pin "7") (pinfunction "7_7") (pintype "passive"))
    )
    (net (code "96") (name "/TRST") (class "Default")
      (node (ref "DD1") (pin "134") (pinfunction "PB4/NJTRST_134") (pintype "passive"))
      (node (ref "X1") (pin "3") (pinfunction "3_3") (pintype "passive"))
    )
    (net (code "97") (name "/T_MARK") (class "Default")
      (node (ref "DD1") (pin "12") (pinfunction "PF2_12") (pintype "passive"))
      (node (ref "DD2") (pin "3") (pinfunction "TIMEMARK_3") (pintype "passive"))
    )
    (net (code "98") (name "/T_SENSE_A_1") (class "Default")
      (node (ref "DD1") (pin "47") (pinfunction "PB1_47") (pintype "passive"))
    )
    (net (code "99") (name "/T_SENSE_A_2") (class "Default")
      (node (ref "DD1") (pin "42") (pinfunction "PA6_42") (pintype "passive"))
    )
    (net (code "100") (name "/T_SENSE_B_1") (class "Default")
      (node (ref "DD1") (pin "49") (pinfunction "PF11_49") (pintype "passive"))
    )
    (net (code "101") (name "/T_SENSE_B_2") (class "Default")
      (node (ref "DD1") (pin "50") (pinfunction "PF12_50") (pintype "passive"))
    )
    (net (code "102") (name "/VM_A_DIV") (class "Default")
      (node (ref "DD1") (pin "46") (pinfunction "PB0_46") (pintype "passive"))
    )
    (net (code "103") (name "/VM_B_DIV") (class "Default")
      (node (ref "DD1") (pin "37") (pinfunction "PA3_37") (pintype "passive"))
    )
    (net (code "104") (name "GND") (class "Default")
      (node (ref "C1") (pin "1") (pinfunction "1_1") (pintype "passive"))
      (node (ref "C10") (pin "1") (pinfunction "1_1") (pintype "passive"))
      (node (ref "C11") (pin "1") (pinfunction "1_1") (pintype "passive"))
      (node (ref "C12") (pin "1") (pinfunction "1_1") (pintype "passive"))
      (node (ref "C13") (pin "1") (pinfunction "1_1") (pintype "passive"))
      (node (ref "C14") (pin "1") (pinfunction "1_1") (pintype "passive"))
      (node (ref "C15") (pin "1") (pinfunction "1_1") (pintype "passive"))
      (node (ref "C16") (pin "1") (pinfunction "1_1") (pintype "passive"))
      (node (ref "C17") (pin "1") (pinfunction "1_1") (pintype "passive"))
      (node (ref "C18") (pin "1") (pinfunction "1_1") (pintype "passive"))
      (node (ref "C19") (pin "1") (pinfunction "1_1") (pintype "passive"))
      (node (ref "C2") (pin "1") (pinfunction "1_1") (pintype "passive"))
      (node (ref "C20") (pin "1") (pinfunction "1_1") (pintype "passive"))
      (node (ref "C21") (pin "1") (pinfunction "1_1") (pintype "passive"))
      (node (ref "C22") (pin "1") (pinfunction "1_1") (pintype "passive"))
      (node (ref "C23") (pin "1") (pinfunction "1_1") (pintype "passive"))
      (node (ref "C24") (pin "1") (pinfunction "1_1") (pintype "passive"))
      (node (ref "C3") (pin "1") (pinfunction "1_1") (pintype "passive"))
      (node (ref "C4") (pin "1") (pinfunction "1_1") (pintype "passive"))
      (node (ref "C5") (pin "1") (pinfunction "1_1") (pintype "passive"))
      (node (ref "C6") (pin "1") (pinfunction "1_1") (pintype "passive"))
      (node (ref "C68") (pin "1") (pinfunction "1_1") (pintype "passive"))
      (node (ref "C69") (pin "1") (pinfunction "1_1") (pintype "passive"))
      (node (ref "C7") (pin "1") (pinfunction "1_1") (pintype "passive"))
      (node (ref "C8") (pin "1") (pinfunction "1_1") (pintype "passive"))
      (node (ref "C9") (pin "1") (pinfunction "1_1") (pintype "passive"))
      (node (ref "C98") (pin "1") (pinfunction "1_1") (pintype "passive"))
      (node (ref "C99") (pin "1") (pinfunction "1_1") (pintype "passive"))
      (node (ref "DD1") (pin "107") (pinfunction "VSS_107") (pintype "passive"))
      (node (ref "DD1") (pin "120") (pinfunction "VSS_120") (pintype "passive"))
      (node (ref "DD1") (pin "130") (pinfunction "VSS_130") (pintype "passive"))
      (node (ref "DD1") (pin "16") (pinfunction "VSS_16") (pintype "passive"))
      (node (ref "DD1") (pin "31") (pinfunction "VSSA_31") (pintype "passive"))
      (node (ref "DD1") (pin "38") (pinfunction "VSS_38") (pintype "passive"))
      (node (ref "DD1") (pin "51") (pinfunction "VSS_51") (pintype "passive"))
      (node (ref "DD1") (pin "61") (pinfunction "VSS_61") (pintype "passive"))
      (node (ref "DD1") (pin "83") (pinfunction "VSS_83") (pintype "passive"))
      (node (ref "DD1") (pin "94") (pinfunction "VSS_94") (pintype "passive"))
      (node (ref "DD13") (pin "8") (pinfunction "GND_1_8") (pintype "passive"))
      (node (ref "DD13") (pin "9") (pinfunction "GND_2_9") (pintype "passive"))
      (node (ref "DD2") (pin "10") (pinfunction "GND_10") (pintype "passive"))
      (node (ref "DD2") (pin "12") (pinfunction "GND_12") (pintype "passive"))
      (node (ref "DD2") (pin "13") (pinfunction "GND_13") (pintype "passive"))
      (node (ref "DD2") (pin "24") (pinfunction "GND_24") (pintype "passive"))
      (node (ref "DD3") (pin "10") (pinfunction "GND_10") (pintype "passive"))
      (node (ref "DD3") (pin "12") (pinfunction "GND_12") (pintype "passive"))
      (node (ref "DD3") (pin "13") (pinfunction "GND_13") (pintype "passive"))
      (node (ref "DD3") (pin "16") (pinfunction "GND_16") (pintype "passive"))
      (node (ref "DD3") (pin "5") (pinfunction "GND_5") (pintype "passive"))
      (node (ref "DD4") (pin "2") (pinfunction "GND_2") (pintype "passive"))
      (node (ref "DD5") (pin "2") (pinfunction "GND_2") (pintype "passive"))
      (node (ref "R10") (pin "1") (pinfunction "1_1") (pintype "passive"))
      (node (ref "R11") (pin "2") (pinfunction "2_2") (pintype "passive"))
      (node (ref "R8") (pin "2") (pinfunction "2_2") (pintype "passive"))
      (node (ref "VT1") (pin "2") (pinfunction "S_2") (pintype "passive"))
      (node (ref "VT2") (pin "2") (pinfunction "S_2") (pintype "passive"))
      (node (ref "X1") (pin "10") (pinfunction "10_10") (pintype "passive"))
      (node (ref "X1") (pin "12") (pinfunction "12_12") (pintype "passive"))
      (node (ref "X1") (pin "14") (pinfunction "14_14") (pintype "passive"))
      (node (ref "X1") (pin "16") (pinfunction "16_16") (pintype "passive"))
      (node (ref "X1") (pin "18") (pinfunction "18_18") (pintype "passive"))
      (node (ref "X1") (pin "20") (pinfunction "20_20") (pintype "passive"))
      (node (ref "X1") (pin "4") (pinfunction "4_4") (pintype "passive"))
      (node (ref "X1") (pin "6") (pinfunction "6_6") (pintype "passive"))
      (node (ref "X1") (pin "8") (pinfunction "8_8") (pintype "passive"))
      (node (ref "X14") (pin "1") (pinfunction "1_1") (pintype "passive"))
      (node (ref "X2") (pin "1") (pinfunction "GND_1") (pintype "passive"))
      (node (ref "X2") (pin "2") (pinfunction "GND_2") (pintype "passive"))
      (node (ref "X2") (pin "3") (pinfunction "GND_3") (pintype "passive"))
      (node (ref "X2") (pin "4") (pinfunction "GND_4") (pintype "passive"))
    )
    (net (code "105") (name "Net-(C5-Pad2)") (class "Default")
      (node (ref "C5") (pin "2") (pinfunction "2_2") (pintype "passive"))
      (node (ref "C6") (pin "2") (pinfunction "2_2") (pintype "passive"))
      (node (ref "DD1") (pin "106") (pinfunction "VCAP_106") (pintype "passive"))
      (node (ref "DD1") (pin "71") (pinfunction "VCAP_71") (pintype "passive"))
    )
    (net (code "106") (name "Net-(DD1A-BOOT0)") (class "Default")
      (node (ref "DD1") (pin "138") (pinfunction "BOOT0_138") (pintype "passive"))
      (node (ref "R11") (pin "1") (pinfunction "1_1") (pintype "passive"))
      (node (ref "R12") (pin "2") (pinfunction "2_2") (pintype "passive"))
    )
    (net (code "107") (name "Net-(DD1A-PB2)") (class "Default")
      (node (ref "DD1") (pin "48") (pinfunction "PB2_48") (pintype "passive"))
      (node (ref "R10") (pin "2") (pinfunction "2_2") (pintype "passive"))
      (node (ref "R9") (pin "1") (pinfunction "1_1") (pintype "passive"))
    )
    (net (code "108") (name "Net-(DD1A-PC14{slash}OSC32_IN)") (class "Default")
      (node (ref "C7") (pin "2") (pinfunction "2_2") (pintype "passive"))
      (node (ref "DD1") (pin "8") (pinfunction "PC14/OSC32_IN_8") (pintype "passive"))
      (node (ref "Z1") (pin "1") (pinfunction "1_1") (pintype "passive"))
    )
    (net (code "109") (name "Net-(DD1A-PC15{slash}OSC32_OUT)") (class "Default")
      (node (ref "C8") (pin "2") (pinfunction "2_2") (pintype "passive"))
      (node (ref "DD1") (pin "9") (pinfunction "PC15/OSC32_OUT_9") (pintype "passive"))
      (node (ref "Z1") (pin "2") (pinfunction "2_2") (pintype "passive"))
    )
    (net (code "110") (name "Net-(DD1A-PE13)") (class "Default")
      (node (ref "DD1") (pin "66") (pinfunction "PE13_66") (pintype "passive"))
      (node (ref "HL1") (pin "1") (pinfunction "A_1") (pintype "passive"))
    )
    (net (code "111") (name "Net-(DD1A-PE14)") (class "Default")
      (node (ref "DD1") (pin "67") (pinfunction "PE14_67") (pintype "passive"))
      (node (ref "HL2") (pin "1") (pinfunction "A_1") (pintype "passive"))
    )
    (net (code "112") (name "Net-(DD1A-PE15)") (class "Default")
      (node (ref "DD1") (pin "68") (pinfunction "PE15_68") (pintype "passive"))
      (node (ref "HL3") (pin "1") (pinfunction "A_1") (pintype "passive"))
    )
    (net (code "113") (name "Net-(DD1B-VBAT)") (class "Default")
      (node (ref "C3") (pin "2") (pinfunction "2_2") (pintype "passive"))
      (node (ref "DD1") (pin "6") (pinfunction "VBAT_6") (pintype "passive"))
    )
    (net (code "114") (name "Net-(DD2-RFIN)") (class "Default")
      (node (ref "C68") (pin "2") (pinfunction "2_2") (pintype "passive"))
      (node (ref "DD2") (pin "11") (pinfunction "RFIN_11") (pintype "passive"))
      (node (ref "R76") (pin "2") (pinfunction "2_2") (pintype "passive"))
    )
    (net (code "115") (name "Net-(DD2-VCC)") (class "Default")
      (node (ref "C2") (pin "2") (pinfunction "2_2") (pintype "passive"))
      (node (ref "DD2") (pin "23") (pinfunction "VCC_23") (pintype "passive"))
      (node (ref "L1") (pin "1") (pinfunction "1_1") (pintype "passive"))
    )
    (net (code "116") (name "Net-(DD2-VCCRF)") (class "Default")
      (node (ref "C4") (pin "2") (pinfunction "2_2") (pintype "passive"))
      (node (ref "DD2") (pin "9") (pinfunction "VCCRF_9") (pintype "passive"))
      (node (ref "L2") (pin "1") (pinfunction "1_1") (pintype "passive"))
    )
    (net (code "117") (name "Net-(DD3-VDDIO)") (class "Default")
      (node (ref "C10") (pin "2") (pinfunction "2_2") (pintype "passive"))
      (node (ref "C9") (pin "2") (pinfunction "2_2") (pintype "passive"))
      (node (ref "DD3") (pin "1") (pinfunction "VDDIO_1") (pintype "passive"))
      (node (ref "DD3") (pin "14") (pinfunction "VDD_14") (pintype "passive"))
      (node (ref "DD3") (pin "15") (pinfunction "VDD_15") (pintype "passive"))
      (node (ref "L3") (pin "1") (pinfunction "1_1") (pintype "passive"))
    )
    (net (code "118") (name "Net-(DD4-OUT)") (class "Default")
      (node (ref "DD4") (pin "3") (pinfunction "OUT_3") (pintype "passive"))
      (node (ref "R13") (pin "2") (pinfunction "2_2") (pintype "passive"))
    )
    (net (code "119") (name "Net-(DD5-OUT)") (class "Default")
      (node (ref "DD5") (pin "3") (pinfunction "OUT_3") (pintype "passive"))
      (node (ref "R14") (pin "2") (pinfunction "2_2") (pintype "passive"))
      (node (ref "R15") (pin "2") (pinfunction "2_2") (pintype "passive"))
    )
    (net (code "120") (name "Net-(DD13-B1)") (class "Default")
      (node (ref "DD13") (pin "15") (pinfunction "B1_15") (pintype "passive"))
      (node (ref "VT1") (pin "1") (pinfunction "G_1") (pintype "passive"))
    )
    (net (code "121") (name "Net-(DD13-B2)") (class "Default")
      (node (ref "DD13") (pin "14") (pinfunction "B2_14") (pintype "passive"))
      (node (ref "VT2") (pin "1") (pinfunction "G_1") (pintype "passive"))
    )
    (net (code "122") (name "Net-(HL1-K)") (class "Default")
      (node (ref "HL1") (pin "2") (pinfunction "K_2") (pintype "passive"))
      (node (ref "R5") (pin "2") (pinfunction "2_2") (pintype "passive"))
    )
    (net (code "123") (name "Net-(HL2-K)") (class "Default")
      (node (ref "HL2") (pin "2") (pinfunction "K_2") (pintype "passive"))
      (node (ref "R6") (pin "2") (pinfunction "2_2") (pintype "passive"))
    )
    (net (code "124") (name "Net-(HL3-K)") (class "Default")
      (node (ref "HL3") (pin "2") (pinfunction "K_2") (pintype "passive"))
      (node (ref "R7") (pin "2") (pinfunction "2_2") (pintype "passive"))
    )
    (net (code "125") (name "Net-(J1-Pad1)") (class "Default")
      (node (ref "J1") (pin "1") (pinfunction "1_1") (pintype "passive"))
      (node (ref "J2") (pin "1") (pinfunction "1_1") (pintype "passive"))
      (node (ref "X14") (pin "6") (pinfunction "6_6") (pintype "passive"))
    )
    (net (code "126") (name "unconnected-(DD1A-PA0-Pad34)") (class "Default")
      (node (ref "DD1") (pin "34") (pinfunction "PA0_34") (pintype "passive"))
    )
    (net (code "127") (name "unconnected-(DD1A-PA8-Pad100)") (class "Default")
      (node (ref "DD1") (pin "100") (pinfunction "PA8_100") (pintype "passive"))
    )
    (net (code "128") (name "unconnected-(DD1A-PA10-Pad102)") (class "Default")
      (node (ref "DD1") (pin "102") (pinfunction "PA10_102") (pintype "passive"))
    )
    (net (code "129") (name "unconnected-(DD1A-PB5-Pad135)") (class "Default")
      (node (ref "DD1") (pin "135") (pinfunction "PB5_135") (pintype "passive"))
    )
    (net (code "130") (name "unconnected-(DD1A-PC0-Pad26)") (class "Default")
      (node (ref "DD1") (pin "26") (pinfunction "PC0_26") (pintype "passive"))
    )
    (net (code "131") (name "unconnected-(DD1A-PC6-Pad96)") (class "Default")
      (node (ref "DD1") (pin "96") (pinfunction "PC6_96") (pintype "passive"))
    )
    (net (code "132") (name "unconnected-(DD1A-PC13-Pad7)") (class "Default")
      (node (ref "DD1") (pin "7") (pinfunction "PC13_7") (pintype "passive"))
    )
    (net (code "133") (name "unconnected-(DD1A-PD1-Pad115)") (class "Default")
      (node (ref "DD1") (pin "115") (pinfunction "PD1_115") (pintype "passive"))
    )
    (net (code "134") (name "unconnected-(DD1A-PD3-Pad117)") (class "Default")
      (node (ref "DD1") (pin "117") (pinfunction "PD3_117") (pintype "passive"))
    )
    (net (code "135") (name "unconnected-(DD1A-PD7-Pad123)") (class "Default")
      (node (ref "DD1") (pin "123") (pinfunction "PD7_123") (pintype "passive"))
    )
    (net (code "136") (name "unconnected-(DD1A-PD14-Pad85)") (class "Default")
      (node (ref "DD1") (pin "85") (pinfunction "PD14_85") (pintype "passive"))
    )
    (net (code "137") (name "unconnected-(DD1A-PD15-Pad86)") (class "Default")
      (node (ref "DD1") (pin "86") (pinfunction "PD15_86") (pintype "passive"))
    )
    (net (code "138") (name "unconnected-(DD1A-PE0-Pad141)") (class "Default")
      (node (ref "DD1") (pin "141") (pinfunction "PE0_141") (pintype "passive"))
    )
    (net (code "139") (name "unconnected-(DD1A-PE7-Pad58)") (class "Default")
      (node (ref "DD1") (pin "58") (pinfunction "PE7_58") (pintype "passive"))
    )
    (net (code "140") (name "unconnected-(DD1A-PE8-Pad59)") (class "Default")
      (node (ref "DD1") (pin "59") (pinfunction "PE8_59") (pintype "passive"))
    )
    (net (code "141") (name "unconnected-(DD1A-PG10-Pad125)") (class "Default")
      (node (ref "DD1") (pin "125") (pinfunction "PG10_125") (pintype "passive"))
    )
    (net (code "142") (name "unconnected-(DD1A-PG15-Pad132)") (class "Default")
      (node (ref "DD1") (pin "132") (pinfunction "PG15_132") (pintype "passive"))
    )
    (net (code "143") (name "unconnected-(DD1A-PH0{slash}OSC_OUT-Pad24)") (class "Default")
      (node (ref "DD1") (pin "24") (pinfunction "PH0/OSC_OUT_24") (pintype "passive"))
    )
    (net (code "144") (name "unconnected-(DD2-MISO-Pad15)") (class "Default")
      (node (ref "DD2") (pin "15") (pinfunction "MISO_15") (pintype "passive"))
    )
    (net (code "145") (name "unconnected-(DD2-MOSI-Pad14)") (class "Default")
      (node (ref "DD2") (pin "14") (pinfunction "MOSI_14") (pintype "passive"))
    )
    (net (code "146") (name "unconnected-(DD2-SCL-Pad19)") (class "Default")
      (node (ref "DD2") (pin "19") (pinfunction "SCL_19") (pintype "passive"))
    )
    (net (code "147") (name "unconnected-(DD2-SCLK-Pad16)") (class "Default")
      (node (ref "DD2") (pin "16") (pinfunction "SCLK_16") (pintype "passive"))
    )
    (net (code "148") (name "unconnected-(DD2-SCS-Pad2)") (class "Default")
      (node (ref "DD2") (pin "2") (pinfunction "SCS_2") (pintype "passive"))
    )
    (net (code "149") (name "unconnected-(DD2-SDA-Pad18)") (class "Default")
      (node (ref "DD2") (pin "18") (pinfunction "SDA_18") (pintype "passive"))
    )
    (net (code "150") (name "unconnected-(DD2-VBACK-Pad22)") (class "Default")
      (node (ref "DD2") (pin "22") (pinfunction "VBACK_22") (pintype "passive"))
    )
    (net (code "151") (name "unconnected-(DD4-E{slash}D-Pad1)") (class "Default")
      (node (ref "DD4") (pin "1") (pinfunction "E/D_1") (pintype "passive"))
    )
    (net (code "152") (name "unconnected-(DD5-E{slash}D-Pad1)") (class "Default")
      (node (ref "DD5") (pin "1") (pinfunction "E/D_1") (pintype "passive"))
    )
    (net (code "153") (name "unconnected-(DD13-A5-Pad6)") (class "Default")
      (node (ref "DD13") (pin "6") (pinfunction "A5_6") (pintype "passive"))
    )
    (net (code "154") (name "unconnected-(DD13-A6-Pad7)") (class "Default")
      (node (ref "DD13") (pin "7") (pinfunction "A6_7") (pintype "passive"))
    )
    (net (code "155") (name "unconnected-(DD13-B5-Pad11)") (class "Default")
      (node (ref "DD13") (pin "11") (pinfunction "B5_11") (pintype "passive"))
    )
    (net (code "156") (name "unconnected-(DD13-B6-Pad10)") (class "Default")
      (node (ref "DD13") (pin "10") (pinfunction "B6_10") (pintype "passive"))
    )
    (net (code "157") (name "unconnected-(X1-Pad11)") (class "Default")
      (node (ref "X1") (pin "11") (pinfunction "11_11") (pintype "passive"))
    )
    (net (code "158") (name "unconnected-(X1-Pad17)") (class "Default")
      (node (ref "X1") (pin "17") (pinfunction "17_17") (pintype "passive"))
    )
    (net (code "159") (name "unconnected-(X1-Pad19)") (class "Default")
      (node (ref "X1") (pin "19") (pinfunction "19_19") (pintype "passive"))
    )
  )
)
